# Netzteil_Darlington_v2_Frontpanel.net
KiCad netlist of a schematic drawn in EAGLE
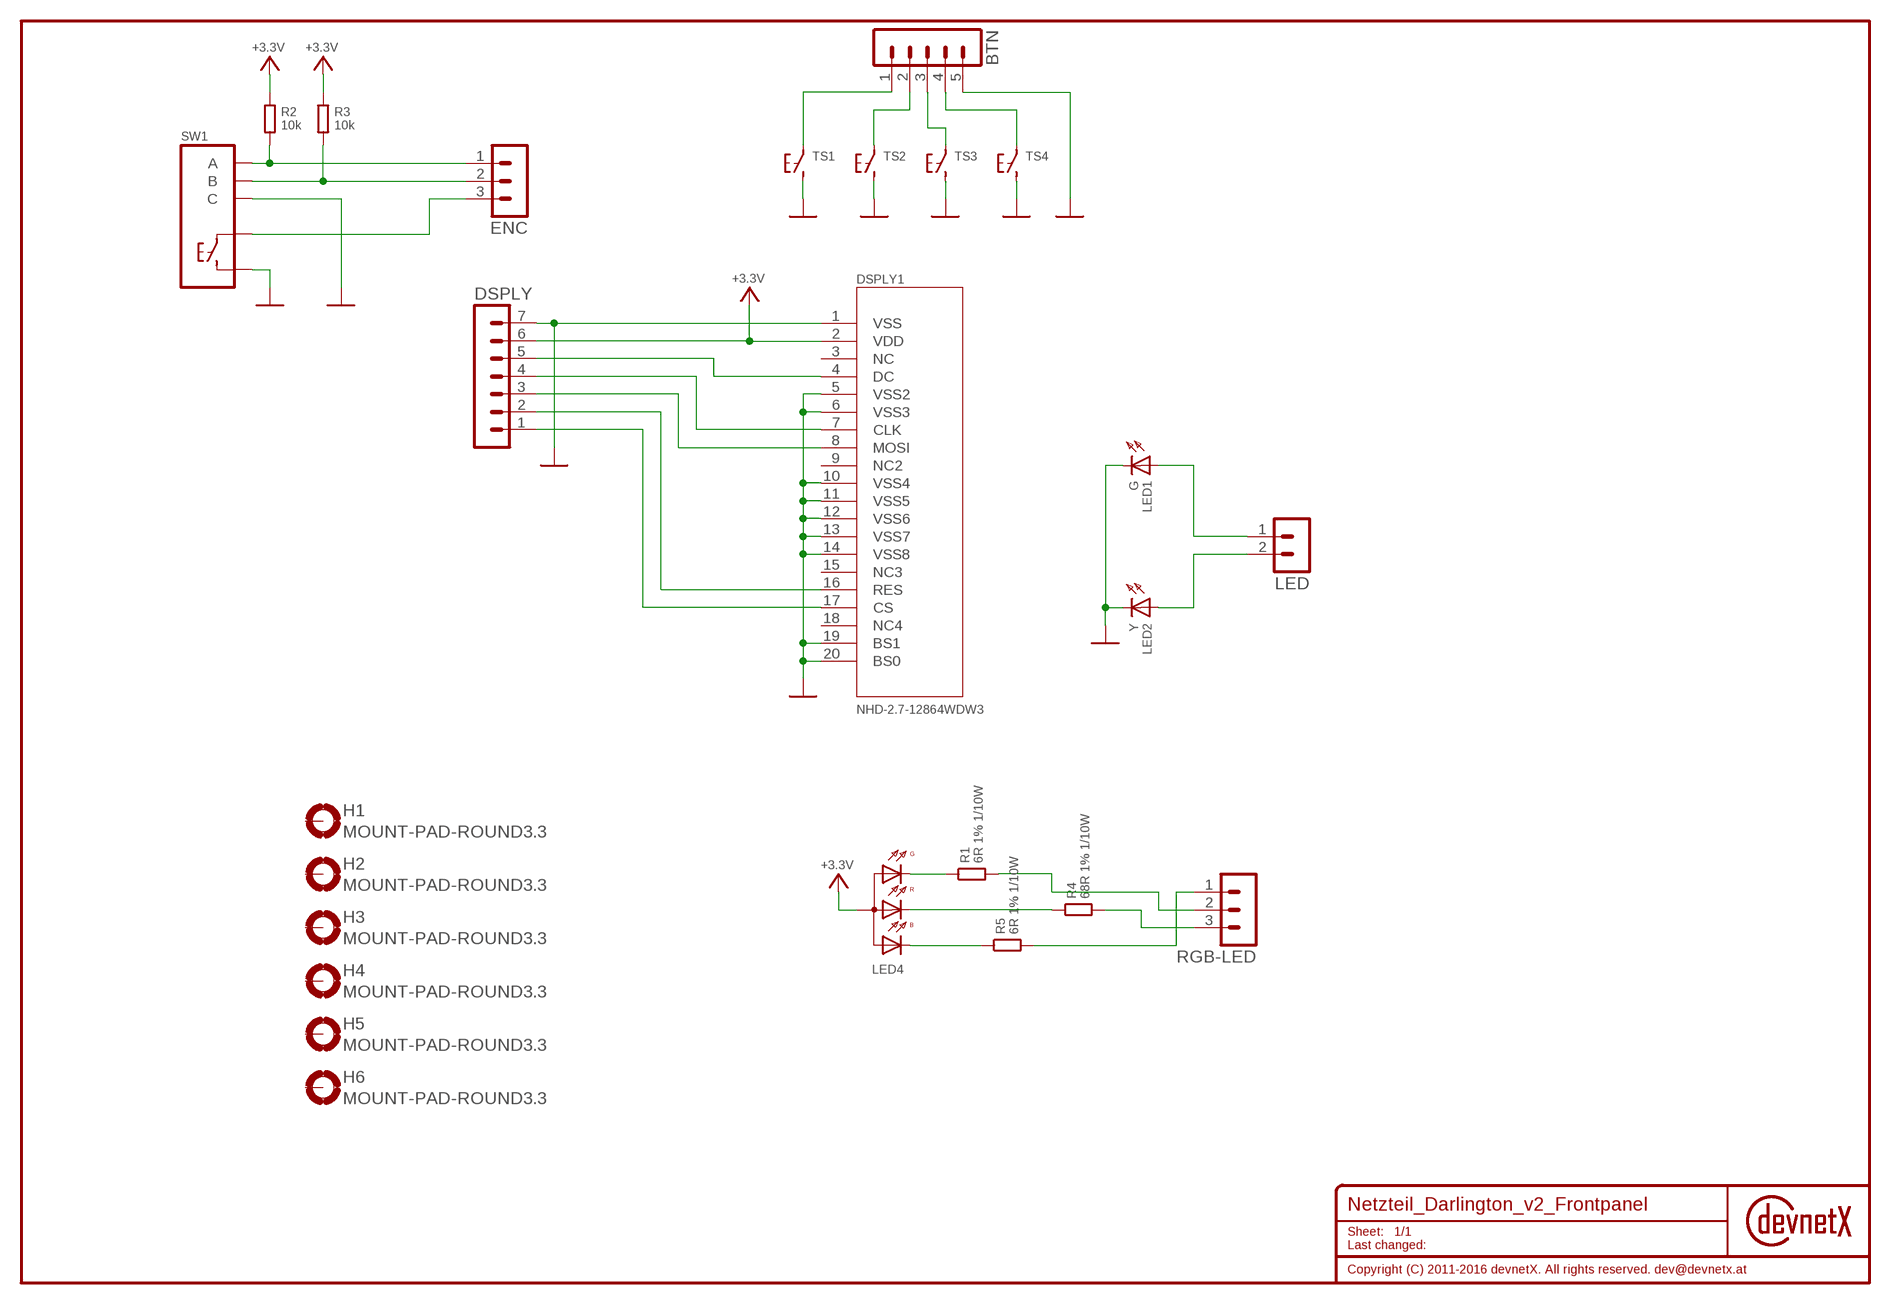
[diagram p0: schematic, sheet 1]

(export (version "E")
  (design (tool "Eeschema 10.0.6"))
  (components
    (comp (ref "BTN")
      (value "JST-PH-2.0-5P")
      (footprint "eagle-import:JST-PH-2.0-5P")
      (libsource (lib "eagle-import") (part "JST-PH-2.0-5P"))
    )
    (comp (ref "DNX-NAME-1")
      (value "DOC-R1.27")
      (footprint "eagle-import:DRAWINGNAME-1.27")
      (libsource (lib "eagle-import") (part "DOC-R1.27"))
    )
    (comp (ref "DSPLY")
      (value "JST-PH-2.0-7P")
      (footprint "eagle-import:JST-PH-2.0-7P")
      (libsource (lib "eagle-import") (part "JST-PH-2.0-7P"))
    )
    (comp (ref "DSPLY1")
      (value "NHD-2.7-12864WDW3")
      (footprint "eagle-import:NHD-2.7-12864WDW3")
      (libsource (lib "eagle-import") (part "NHD-2.7-12864WDW3"))
    )
    (comp (ref "ENC")
      (value "JST-PH-2.0-3P")
      (footprint "eagle-import:JST-PH-2.0-3P")
      (libsource (lib "eagle-import") (part "JST-PH-2.0-3P"))
    )
    (comp (ref "H1")
      (value "MOUNT-PAD-ROUND3.3")
      (footprint "eagle-import:3,3-PAD")
      (libsource (lib "eagle-import") (part "MOUNT-PAD-ROUND3.3"))
    )
    (comp (ref "H2")
      (value "MOUNT-PAD-ROUND3.3")
      (footprint "eagle-import:3,3-PAD")
      (libsource (lib "eagle-import") (part "MOUNT-PAD-ROUND3.3"))
    )
    (comp (ref "H3")
      (value "MOUNT-PAD-ROUND3.3")
      (footprint "eagle-import:3,3-PAD")
      (libsource (lib "eagle-import") (part "MOUNT-PAD-ROUND3.3"))
    )
    (comp (ref "H4")
      (value "MOUNT-PAD-ROUND3.3")
      (footprint "eagle-import:3,3-PAD")
      (libsource (lib "eagle-import") (part "MOUNT-PAD-ROUND3.3"))
    )
    (comp (ref "H5")
      (value "MOUNT-PAD-ROUND3.3")
      (footprint "eagle-import:3,3-PAD")
      (libsource (lib "eagle-import") (part "MOUNT-PAD-ROUND3.3"))
    )
    (comp (ref "H6")
      (value "MOUNT-PAD-ROUND3.3")
      (footprint "eagle-import:3,3-PAD")
      (libsource (lib "eagle-import") (part "MOUNT-PAD-ROUND3.3"))
    )
    (comp (ref "LED")
      (value "JST-PH-2.0-2P")
      (footprint "eagle-import:JST-PH-2.0-2P")
      (libsource (lib "eagle-import") (part "JST-PH-2.0-2P"))
    )
    (comp (ref "LED1")
      (value "G")
      (footprint "eagle-import:LED0805")
      (libsource (lib "eagle-import") (part "LED0805"))
    )
    (comp (ref "LED2")
      (value "Y")
      (footprint "eagle-import:LED0805")
      (libsource (lib "eagle-import") (part "LED0805"))
    )
    (comp (ref "LED4")
      (value "LED-RGB")
      (footprint "eagle-import:C1411")
      (libsource (lib "eagle-import") (part "LED-RGB"))
    )
    (comp (ref "R1")
      (value "6R 1% 1/10W")
      (footprint "eagle-import:C0805K")
      (libsource (lib "eagle-import") (part "R-SMD0805"))
    )
    (comp (ref "R2")
      (value "10k")
      (footprint "eagle-import:C0805K")
      (libsource (lib "eagle-import") (part "R-SMD0805"))
    )
    (comp (ref "R3")
      (value "10k")
      (footprint "eagle-import:C0805K")
      (libsource (lib "eagle-import") (part "R-SMD0805"))
    )
    (comp (ref "R4")
      (value "68R 1% 1/10W")
      (footprint "eagle-import:C0805K")
      (libsource (lib "eagle-import") (part "R-SMD0805"))
    )
    (comp (ref "R5")
      (value "6R 1% 1/10W")
      (footprint "eagle-import:C0805K")
      (libsource (lib "eagle-import") (part "R-SMD0805"))
    )
    (comp (ref "RGB-LED")
      (value "JST-PH-2.0-3P")
      (footprint "eagle-import:JST-PH-2.0-3P")
      (libsource (lib "eagle-import") (part "JST-PH-2.0-3P"))
    )
    (comp (ref "SW1")
      (value "EC12E-SW")
      (footprint "eagle-import:EC12E-SW")
      (libsource (lib "eagle-import") (part "EC12E-SW"))
    )
    (comp (ref "TS1")
      (value "TS1B3F-10XX")
      (footprint "eagle-import:B3F-10XX")
      (libsource (lib "eagle-import") (part "TS1B3F-10XX"))
    )
    (comp (ref "TS2")
      (value "TS1B3F-10XX")
      (footprint "eagle-import:B3F-10XX")
      (libsource (lib "eagle-import") (part "TS1B3F-10XX"))
    )
    (comp (ref "TS3")
      (value "TS1B3F-10XX")
      (footprint "eagle-import:B3F-10XX")
      (libsource (lib "eagle-import") (part "TS1B3F-10XX"))
    )
    (comp (ref "TS4")
      (value "TS1B3F-10XX")
      (footprint "eagle-import:B3F-10XX")
      (libsource (lib "eagle-import") (part "TS1B3F-10XX"))
    )
  )
  (nets
    (net (code "1") (name "+3.3V") (class "Default")
      (node (ref "DSPLY") (pin "6") (pinfunction "6_6") (pintype "passive"))
      (node (ref "DSPLY1") (pin "2") (pinfunction "VDD_2") (pintype "power_in"))
      (node (ref "LED4") (pin "1") (pinfunction "A_1") (pintype "passive"))
      (node (ref "R2") (pin "1") (pinfunction "1_1") (pintype "passive"))
      (node (ref "R3") (pin "1") (pinfunction "1_1") (pintype "passive"))
    )
    (net (code "2") (name "Net-(BTN-Pad1)") (class "Default")
      (node (ref "BTN") (pin "1") (pinfunction "1_1") (pintype "passive"))
      (node (ref "TS1") (pin "1") (pinfunction "1_1") (pintype "passive"))
    )
    (net (code "3") (name "Net-(BTN-Pad2)") (class "Default")
      (node (ref "BTN") (pin "2") (pinfunction "2_2") (pintype "passive"))
      (node (ref "TS2") (pin "1") (pinfunction "1_1") (pintype "passive"))
    )
    (net (code "4") (name "Net-(BTN-Pad3)") (class "Default")
      (node (ref "BTN") (pin "3") (pinfunction "3_3") (pintype "passive"))
      (node (ref "TS3") (pin "1") (pinfunction "1_1") (pintype "passive"))
    )
    (net (code "5") (name "Net-(BTN-Pad4)") (class "Default")
      (node (ref "BTN") (pin "4") (pinfunction "4_4") (pintype "passive"))
      (node (ref "TS4") (pin "1") (pinfunction "1_1") (pintype "passive"))
    )
    (net (code "6") (name "Net-(DSPLY1-CLK)") (class "Default")
      (node (ref "DSPLY") (pin "4") (pinfunction "4_4") (pintype "passive"))
      (node (ref "DSPLY1") (pin "7") (pinfunction "CLK_7") (pintype "bidirectional"))
    )
    (net (code "7") (name "Net-(DSPLY1-CS)") (class "Default")
      (node (ref "DSPLY") (pin "1") (pinfunction "1_1") (pintype "passive"))
      (node (ref "DSPLY1") (pin "17") (pinfunction "CS_17") (pintype "bidirectional"))
    )
    (net (code "8") (name "Net-(DSPLY1-DC)") (class "Default")
      (node (ref "DSPLY") (pin "5") (pinfunction "5_5") (pintype "passive"))
      (node (ref "DSPLY1") (pin "4") (pinfunction "DC_4") (pintype "bidirectional"))
    )
    (net (code "9") (name "Net-(DSPLY1-MOSI)") (class "Default")
      (node (ref "DSPLY") (pin "3") (pinfunction "3_3") (pintype "passive"))
      (node (ref "DSPLY1") (pin "8") (pinfunction "MOSI_8") (pintype "bidirectional"))
    )
    (net (code "10") (name "Net-(DSPLY1-RES)") (class "Default")
      (node (ref "DSPLY") (pin "2") (pinfunction "2_2") (pintype "passive"))
      (node (ref "DSPLY1") (pin "16") (pinfunction "RES_16") (pintype "bidirectional"))
    )
    (net (code "11") (name "Net-(ENC-Pad1)") (class "Default")
      (node (ref "ENC") (pin "1") (pinfunction "1_1") (pintype "passive"))
      (node (ref "R2") (pin "2") (pinfunction "2_2") (pintype "passive"))
      (node (ref "SW1") (pin "A") (pinfunction "A_A") (pintype "passive"))
    )
    (net (code "12") (name "Net-(ENC-Pad2)") (class "Default")
      (node (ref "ENC") (pin "2") (pinfunction "2_2") (pintype "passive"))
      (node (ref "R3") (pin "2") (pinfunction "2_2") (pintype "passive"))
      (node (ref "SW1") (pin "B") (pinfunction "B_B") (pintype "passive"))
    )
    (net (code "13") (name "Net-(ENC-Pad3)") (class "Default")
      (node (ref "ENC") (pin "3") (pinfunction "3_3") (pintype "passive"))
      (node (ref "SW1") (pin "1") (pinfunction "1_1") (pintype "passive"))
    )
    (net (code "14") (name "Net-(LED-Pad1)") (class "Default")
      (node (ref "LED") (pin "1") (pinfunction "1_1") (pintype "passive"))
      (node (ref "LED1") (pin "A") (pinfunction "A_A") (pintype "passive"))
    )
    (net (code "15") (name "Net-(LED-Pad2)") (class "Default")
      (node (ref "LED") (pin "2") (pinfunction "2_2") (pintype "passive"))
      (node (ref "LED2") (pin "A") (pinfunction "A_A") (pintype "passive"))
    )
    (net (code "16") (name "Net-(LED4-C2)") (class "Default")
      (node (ref "LED4") (pin "2") (pinfunction "C2_2") (pintype "passive"))
      (node (ref "R5") (pin "1") (pinfunction "1_1") (pintype "passive"))
    )
    (net (code "17") (name "Net-(LED4-C3)") (class "Default")
      (node (ref "LED4") (pin "3") (pinfunction "C3_3") (pintype "passive"))
      (node (ref "R4") (pin "1") (pinfunction "1_1") (pintype "passive"))
    )
    (net (code "18") (name "Net-(LED4-C4)") (class "Default")
      (node (ref "LED4") (pin "4") (pinfunction "C4_4") (pintype "passive"))
      (node (ref "R1") (pin "1") (pinfunction "1_1") (pintype "passive"))
    )
    (net (code "19") (name "Net-(R1-Pad2)") (class "Default")
      (node (ref "R1") (pin "2") (pinfunction "2_2") (pintype "passive"))
      (node (ref "RGB-LED") (pin "2") (pinfunction "2_2") (pintype "passive"))
    )
    (net (code "20") (name "Net-(R4-Pad2)") (class "Default")
      (node (ref "R4") (pin "2") (pinfunction "2_2") (pintype "passive"))
      (node (ref "RGB-LED") (pin "3") (pinfunction "3_3") (pintype "passive"))
    )
    (net (code "21") (name "Net-(R5-Pad2)") (class "Default")
      (node (ref "R5") (pin "2") (pinfunction "2_2") (pintype "passive"))
      (node (ref "RGB-LED") (pin "1") (pinfunction "1_1") (pintype "passive"))
    )
    (net (code "22") (name "VSS") (class "Default")
      (node (ref "BTN") (pin "5") (pinfunction "5_5") (pintype "passive"))
      (node (ref "DSPLY") (pin "7") (pinfunction "7_7") (pintype "passive"))
      (node (ref "DSPLY1") (pin "1") (pinfunction "VSS_1") (pintype "power_in"))
      (node (ref "DSPLY1") (pin "10") (pinfunction "VSS4_10") (pintype "power_in"))
      (node (ref "DSPLY1") (pin "11") (pinfunction "VSS5_11") (pintype "power_in"))
      (node (ref "DSPLY1") (pin "12") (pinfunction "VSS6_12") (pintype "power_in"))
      (node (ref "DSPLY1") (pin "13") (pinfunction "VSS7_13") (pintype "power_in"))
      (node (ref "DSPLY1") (pin "14") (pinfunction "VSS8_14") (pintype "power_in"))
      (node (ref "DSPLY1") (pin "19") (pinfunction "BS1_19") (pintype "bidirectional"))
      (node (ref "DSPLY1") (pin "20") (pinfunction "BS0_20") (pintype "bidirectional"))
      (node (ref "DSPLY1") (pin "5") (pinfunction "VSS2_5") (pintype "power_in"))
      (node (ref "DSPLY1") (pin "6") (pinfunction "VSS3_6") (pintype "power_in"))
      (node (ref "LED1") (pin "C") (pinfunction "C_C") (pintype "passive"))
      (node (ref "LED2") (pin "C") (pinfunction "C_C") (pintype "passive"))
      (node (ref "SW1") (pin "2") (pinfunction "2_2") (pintype "passive"))
      (node (ref "SW1") (pin "C") (pinfunction "C_C") (pintype "passive"))
      (node (ref "TS1") (pin "3") (pinfunction "2_3") (pintype "passive"))
      (node (ref "TS2") (pin "3") (pinfunction "2_3") (pintype "passive"))
      (node (ref "TS3") (pin "3") (pinfunction "2_3") (pintype "passive"))
      (node (ref "TS4") (pin "3") (pinfunction "2_3") (pintype "passive"))
    )
    (net (code "23") (name "unconnected-(DSPLY1-NC-Pad3)") (class "Default")
      (node (ref "DSPLY1") (pin "3") (pinfunction "NC_3") (pintype "no_connect"))
    )
    (net (code "24") (name "unconnected-(DSPLY1-NC2-Pad9)") (class "Default")
      (node (ref "DSPLY1") (pin "9") (pinfunction "NC2_9") (pintype "no_connect"))
    )
    (net (code "25") (name "unconnected-(DSPLY1-NC3-Pad15)") (class "Default")
      (node (ref "DSPLY1") (pin "15") (pinfunction "NC3_15") (pintype "no_connect"))
    )
    (net (code "26") (name "unconnected-(DSPLY1-NC4-Pad18)") (class "Default")
      (node (ref "DSPLY1") (pin "18") (pinfunction "NC4_18") (pintype "no_connect"))
    )
    (net (code "27") (name "unconnected-(H1-MOUNT-PadB3,3)") (class "Default")
      (node (ref "H1") (pin "B3,3") (pinfunction "MOUNT_B3,3") (pintype "passive"))
    )
    (net (code "28") (name "unconnected-(H2-MOUNT-PadB3,3)") (class "Default")
      (node (ref "H2") (pin "B3,3") (pinfunction "MOUNT_B3,3") (pintype "passive"))
    )
    (net (code "29") (name "unconnected-(H3-MOUNT-PadB3,3)") (class "Default")
      (node (ref "H3") (pin "B3,3") (pinfunction "MOUNT_B3,3") (pintype "passive"))
    )
    (net (code "30") (name "unconnected-(H4-MOUNT-PadB3,3)") (class "Default")
      (node (ref "H4") (pin "B3,3") (pinfunction "MOUNT_B3,3") (pintype "passive"))
    )
    (net (code "31") (name "unconnected-(H5-MOUNT-PadB3,3)") (class "Default")
      (node (ref "H5") (pin "B3,3") (pinfunction "MOUNT_B3,3") (pintype "passive"))
    )
    (net (code "32") (name "unconnected-(H6-MOUNT-PadB3,3)") (class "Default")
      (node (ref "H6") (pin "B3,3") (pinfunction "MOUNT_B3,3") (pintype "passive"))
    )
  )
)
